# ESP32S2-new_sensor_device_template.net
KiCad netlist of a schematic drawn in EasyEDA
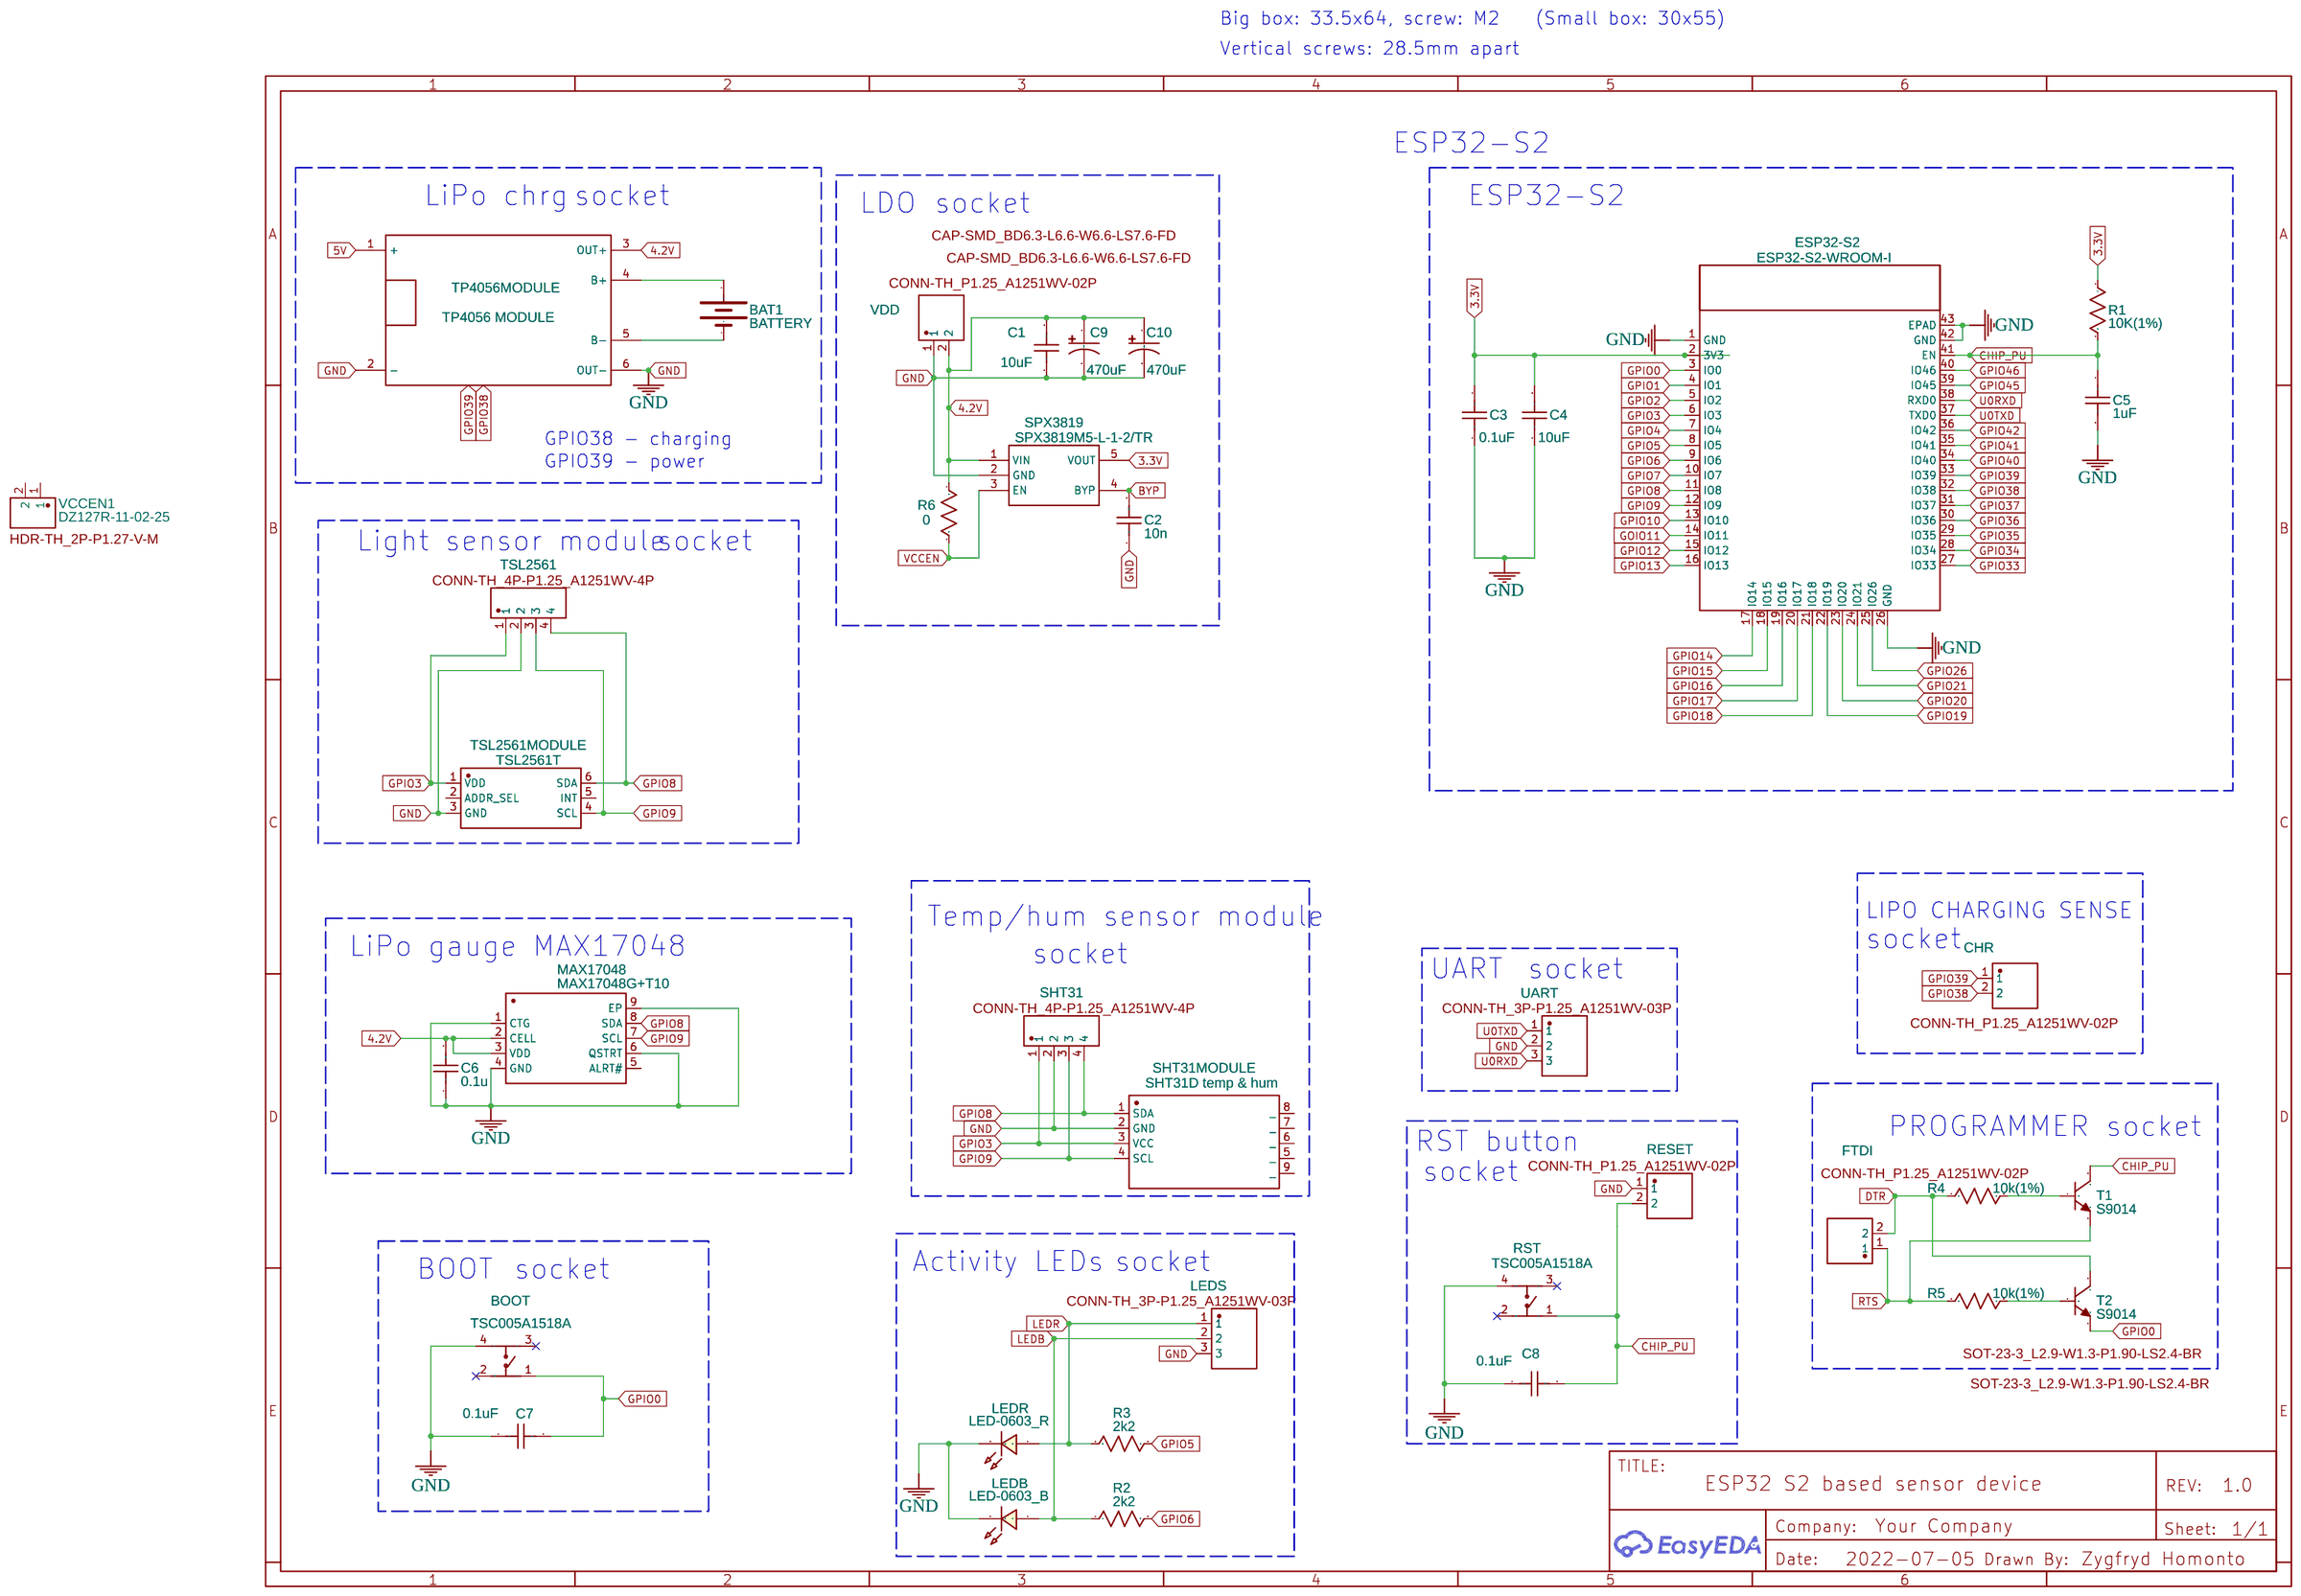
[diagram p0: schematic sheet]

(export (version "E")
  (design (tool "Eeschema 10.0.6"))
  (components
    (comp (ref "BAT1") (value "BATTERY") (libsource (lib "") (part "BATTERY")))
    (comp (ref "BOOT")
      (value "TSC005A1518A")
      (fields (field (name "BOM_Supplier Part") "C2888479"))
      (libsource (lib "") (part "TSC005A1518A"))
    )
    (comp (ref "C1") (value "10uF") (libsource (lib "") (part "C_0201_US_1")))
    (comp (ref "C2") (value "10n") (libsource (lib "") (part "C_0603_US")))
    (comp (ref "C3") (value "0.1uF") (libsource (lib "") (part "C_0201_US_1")))
    (comp (ref "C4") (value "10uF") (libsource (lib "") (part "C_0201_US_1")))
    (comp (ref "C5") (value "1uF") (libsource (lib "") (part "C_0201_US_2")))
    (comp (ref "C6") (value "0.1u") (libsource (lib "") (part "C_0603_US")))
    (comp (ref "C7") (value "0.1uF") (libsource (lib "") (part "C_0201_US")))
    (comp (ref "C8") (value "0.1uF") (libsource (lib "") (part "C_0201_US")))
    (comp (ref "C9")
      (value "470uF")
      (fields
        (field (name "BOM_Manufacturer Part") "BXJ-16V220-6.3*7.7")
        (field (name "BOM_Supplier Part") "C165635")
      )
      (libsource (lib "") (part "BXJ-16V220-6.3*7.7_1"))
    )
    (comp (ref "C10")
      (value "470uF")
      (fields
        (field (name "BOM_Manufacturer Part") "BXJ-16V220-6.3*7.7")
        (field (name "BOM_Supplier Part") "C165635")
      )
      (libsource (lib "") (part "BXJ-16V220-6.3*7.7"))
    )
    (comp (ref "CHR")
      (value "A1251WR-2P")
      (fields (field (name "BOM_Supplier Part") "C225097"))
      (libsource (lib "") (part "A1251WR-2P_3"))
    )
    (comp (ref "ESP32-S2")
      (value "ESP32-S2-WROOM-I")
      (fields (field (name "BOM_Manufacturer Part") "ESP32-S2-WROOM"))
      (libsource (lib "") (part "ESP32-S2-WROOM"))
    )
    (comp (ref "FTDI")
      (value "A1251WR-2P")
      (fields (field (name "BOM_Supplier Part") "C225097"))
      (libsource (lib "") (part "A1251WR-2P"))
    )
    (comp (ref "LEDB")
      (value "LED-0603_B")
      (fields
        (field (name "BOM_Manufacturer Part") "19-217/BHC-ZL1M2RY/3T")
        (field (name "BOM_Supplier Part") "C72041")
      )
      (libsource (lib "") (part "LED-0603_B"))
    )
    (comp (ref "LEDR")
      (value "LED-0603_R")
      (fields
        (field (name "BOM_Manufacturer Part") "19-217/R6C-AL1M2VY/3T")
        (field (name "BOM_Supplier Part") "C72044")
      )
      (libsource (lib "") (part "LED-0603_R"))
    )
    (comp (ref "LEDS")
      (value "A1251WR-3P")
      (fields (field (name "BOM_Supplier Part") "C225098"))
      (libsource (lib "") (part "A1251WR-3P_1"))
    )
    (comp (ref "MAX17048")
      (value "MAX17048G+T10")
      (fields (field (name "BOM_Supplier Part") "C2682616"))
      (libsource (lib "") (part "MAX17048G+T10"))
    )
    (comp (ref "R1") (value "10K(1%)") (libsource (lib "") (part "R_0201_US_1")))
    (comp (ref "R2") (value "2k2") (libsource (lib "") (part "R_0201_US")))
    (comp (ref "R3") (value "2k2") (libsource (lib "") (part "R_0201_US")))
    (comp (ref "R4") (value "10k(1%)") (libsource (lib "") (part "R_0201_US")))
    (comp (ref "R5") (value "10k(1%)") (libsource (lib "") (part "R_0201_US")))
    (comp (ref "R6") (value "0") (libsource (lib "") (part "R_0201_US_1")))
    (comp (ref "RESET")
      (value "A1251WR-2P")
      (fields (field (name "BOM_Supplier Part") "C225097"))
      (libsource (lib "") (part "A1251WR-2P_1"))
    )
    (comp (ref "RST")
      (value "TSC005A1518A")
      (fields (field (name "BOM_Supplier Part") "C2888479"))
      (libsource (lib "") (part "TSC005A1518A_1"))
    )
    (comp (ref "SHT31")
      (value "A1251WR-04P")
      (fields (field (name "BOM_Supplier Part") "C462094"))
      (libsource (lib "") (part "A1251WR-04P_1"))
    )
    (comp (ref "SHT31MODULE")
      (value "SHT31D temp & hum")
      (fields
        (field (name "BOM_Manufacturer Part") "SHT31-DIS-B")
        (field (name "BOM_Supplier Part") "C80862")
      )
      (libsource (lib "") (part "SHT31-DIS-B"))
    )
    (comp (ref "SPX3819")
      (value "SPX3819M5-L-1-2/TR")
      (fields (field (name "BOM_Supplier Part") "C54988"))
      (libsource (lib "") (part "SPX3819M5-L-1-2/TR"))
    )
    (comp (ref "T1")
      (value "S9014")
      (fields
        (field (name "BOM_Manufacturer Part") "S9014LT1 (S9014 J6)")
        (field (name "BOM_Supplier Part") "C2148")
      )
      (libsource (lib "") (part "S9014LT1 (S9014 J6)"))
    )
    (comp (ref "T2")
      (value "S9014")
      (fields
        (field (name "BOM_Manufacturer Part") "S9014LT1 (S9014 J6)")
        (field (name "BOM_Supplier Part") "C2148")
      )
      (libsource (lib "") (part "S9014LT1 (S9014 J6)_1"))
    )
    (comp (ref "TP4056MODULE") (value "TP4056 MODULE") (libsource (lib "") (part "TP4056 MODULE")))
    (comp (ref "TSL2561")
      (value "A1251WR-04P")
      (fields (field (name "BOM_Supplier Part") "C462094"))
      (libsource (lib "") (part "A1251WR-04P"))
    )
    (comp (ref "TSL2561MODULE")
      (value "TSL2561T")
      (fields (field (name "BOM_Supplier Part") "C481878"))
      (libsource (lib "") (part "TSL2561T"))
    )
    (comp (ref "UART")
      (value "A1251WR-3P")
      (fields (field (name "BOM_Supplier Part") "C225098"))
      (libsource (lib "") (part "A1251WR-3P"))
    )
    (comp (ref "VCCEN1")
      (value "DZ127R-11-02-25")
      (fields (field (name "BOM_Supplier Part") "C2935942"))
      (libsource (lib "") (part "DZ127R-11-02-25"))
    )
    (comp (ref "VDD")
      (value "A1251WR-2P")
      (fields (field (name "BOM_Supplier Part") "C225097"))
      (libsource (lib "") (part "A1251WR-2P_2"))
    )
  )
  (nets
    (net (code "1") (name "3.3V") (class "Default")
      (node (ref "C3") (pin "2") (pinfunction "2_2") (pintype "unspecified"))
      (node (ref "C4") (pin "2") (pinfunction "2_2") (pintype "unspecified"))
      (node (ref "ESP32-S2") (pin "2") (pinfunction "3V3_2") (pintype "unspecified"))
      (node (ref "R1") (pin "1") (pinfunction "1_1") (pintype "unspecified"))
      (node (ref "SPX3819") (pin "5") (pinfunction "VOUT_5") (pintype "unspecified"))
    )
    (net (code "2") (name "4.2V") (class "Default")
      (node (ref "C1") (pin "2") (pinfunction "2_2") (pintype "unspecified"))
      (node (ref "C10") (pin "1") (pinfunction "1_1") (pintype "unspecified"))
      (node (ref "C6") (pin "2") (pinfunction "2_2") (pintype "unspecified"))
      (node (ref "C9") (pin "1") (pinfunction "1_1") (pintype "unspecified"))
      (node (ref "MAX17048") (pin "2") (pinfunction "CELL_2") (pintype "unspecified"))
      (node (ref "MAX17048") (pin "3") (pinfunction "VDD_3") (pintype "unspecified"))
      (node (ref "R6") (pin "1") (pinfunction "1_1") (pintype "unspecified"))
      (node (ref "SPX3819") (pin "1") (pinfunction "VIN_1") (pintype "unspecified"))
      (node (ref "TP4056MODULE") (pin "3") (pinfunction "OUT+_3") (pintype "unspecified"))
      (node (ref "VDD") (pin "2") (pinfunction "2_2") (pintype "unspecified"))
    )
    (net (code "3") (name "5V") (class "Default")
      (node (ref "TP4056MODULE") (pin "1") (pinfunction "+_1") (pintype "unspecified"))
    )
    (net (code "4") (name "BYP") (class "Default")
      (node (ref "C2") (pin "2") (pinfunction "2_2") (pintype "unspecified"))
      (node (ref "SPX3819") (pin "4") (pinfunction "BYP_4") (pintype "unspecified"))
    )
    (net (code "5") (name "CHIP_PU") (class "Default")
      (node (ref "C5") (pin "1") (pinfunction "1_1") (pintype "unspecified"))
      (node (ref "C8") (pin "2") (pinfunction "2_2") (pintype "unspecified"))
      (node (ref "ESP32-S2") (pin "41") (pinfunction "EN_41") (pintype "unspecified"))
      (node (ref "R1") (pin "2") (pinfunction "2_2") (pintype "unspecified"))
      (node (ref "RESET") (pin "2") (pinfunction "2_2") (pintype "unspecified"))
      (node (ref "RST") (pin "1") (pinfunction "1_1") (pintype "unspecified"))
      (node (ref "T1") (pin "3") (pinfunction "C_3") (pintype "unspecified"))
    )
    (net (code "6") (name "DTR") (class "Default")
      (node (ref "FTDI") (pin "2") (pinfunction "2_2") (pintype "unspecified"))
      (node (ref "R4") (pin "1") (pinfunction "1_1") (pintype "unspecified"))
      (node (ref "T2") (pin "3") (pinfunction "C_3") (pintype "unspecified"))
    )
    (net (code "7") (name "GND") (class "Default")
      (node (ref "BOOT") (pin "4") (pinfunction "4_4") (pintype "unspecified"))
      (node (ref "C1") (pin "1") (pinfunction "1_1") (pintype "unspecified"))
      (node (ref "C10") (pin "2") (pinfunction "2_2") (pintype "unspecified"))
      (node (ref "C2") (pin "1") (pinfunction "1_1") (pintype "unspecified"))
      (node (ref "C3") (pin "1") (pinfunction "1_1") (pintype "unspecified"))
      (node (ref "C4") (pin "1") (pinfunction "1_1") (pintype "unspecified"))
      (node (ref "C5") (pin "2") (pinfunction "2_2") (pintype "unspecified"))
      (node (ref "C6") (pin "1") (pinfunction "1_1") (pintype "unspecified"))
      (node (ref "C7") (pin "1") (pinfunction "1_1") (pintype "unspecified"))
      (node (ref "C8") (pin "1") (pinfunction "1_1") (pintype "unspecified"))
      (node (ref "C9") (pin "2") (pinfunction "2_2") (pintype "unspecified"))
      (node (ref "ESP32-S2") (pin "1") (pinfunction "GND_1") (pintype "unspecified"))
      (node (ref "ESP32-S2") (pin "26") (pinfunction "GND_26") (pintype "unspecified"))
      (node (ref "ESP32-S2") (pin "42") (pinfunction "GND_42") (pintype "unspecified"))
      (node (ref "ESP32-S2") (pin "43") (pinfunction "EPAD_43") (pintype "unspecified"))
      (node (ref "LEDB") (pin "2") (pinfunction "2_2") (pintype "unspecified"))
      (node (ref "LEDR") (pin "2") (pinfunction "2_2") (pintype "unspecified"))
      (node (ref "LEDS") (pin "3") (pinfunction "3_3") (pintype "unspecified"))
      (node (ref "MAX17048") (pin "1") (pinfunction "CTG_1") (pintype "unspecified"))
      (node (ref "MAX17048") (pin "4") (pinfunction "GND_4") (pintype "unspecified"))
      (node (ref "MAX17048") (pin "6") (pinfunction "QSTRT_6") (pintype "unspecified"))
      (node (ref "MAX17048") (pin "9") (pinfunction "EP_9") (pintype "unspecified"))
      (node (ref "RESET") (pin "1") (pinfunction "1_1") (pintype "unspecified"))
      (node (ref "RST") (pin "4") (pinfunction "4_4") (pintype "unspecified"))
      (node (ref "SHT31") (pin "2") (pinfunction "2_2") (pintype "unspecified"))
      (node (ref "SHT31MODULE") (pin "2") (pinfunction "GND_2") (pintype "unspecified"))
      (node (ref "SPX3819") (pin "2") (pinfunction "GND_2") (pintype "unspecified"))
      (node (ref "TP4056MODULE") (pin "2") (pinfunction "-_2") (pintype "unspecified"))
      (node (ref "TP4056MODULE") (pin "6") (pinfunction "OUT-_6") (pintype "unspecified"))
      (node (ref "TSL2561") (pin "2") (pinfunction "2_2") (pintype "unspecified"))
      (node (ref "TSL2561MODULE") (pin "3") (pinfunction "GND_3") (pintype "unspecified"))
      (node (ref "UART") (pin "2") (pinfunction "2_2") (pintype "unspecified"))
      (node (ref "VDD") (pin "1") (pinfunction "1_1") (pintype "unspecified"))
    )
    (net (code "8") (name "GOIO11") (class "Default")
      (node (ref "ESP32-S2") (pin "14") (pinfunction "IO11_14") (pintype "unspecified"))
    )
    (net (code "9") (name "GPIO0") (class "Default")
      (node (ref "BOOT") (pin "1") (pinfunction "1_1") (pintype "unspecified"))
      (node (ref "C7") (pin "2") (pinfunction "2_2") (pintype "unspecified"))
      (node (ref "ESP32-S2") (pin "3") (pinfunction "IO0_3") (pintype "unspecified"))
      (node (ref "T2") (pin "2") (pinfunction "E_2") (pintype "unspecified"))
    )
    (net (code "10") (name "GPIO1") (class "Default")
      (node (ref "ESP32-S2") (pin "4") (pinfunction "IO1_4") (pintype "unspecified"))
    )
    (net (code "11") (name "GPIO2") (class "Default")
      (node (ref "ESP32-S2") (pin "5") (pinfunction "IO2_5") (pintype "unspecified"))
    )
    (net (code "12") (name "GPIO3") (class "Default")
      (node (ref "ESP32-S2") (pin "6") (pinfunction "IO3_6") (pintype "unspecified"))
      (node (ref "SHT31") (pin "1") (pinfunction "1_1") (pintype "unspecified"))
      (node (ref "SHT31MODULE") (pin "3") (pinfunction "VCC_3") (pintype "unspecified"))
      (node (ref "TSL2561") (pin "1") (pinfunction "1_1") (pintype "unspecified"))
      (node (ref "TSL2561MODULE") (pin "1") (pinfunction "VDD_1") (pintype "unspecified"))
    )
    (net (code "13") (name "GPIO4") (class "Default")
      (node (ref "ESP32-S2") (pin "7") (pinfunction "IO4_7") (pintype "unspecified"))
    )
    (net (code "14") (name "GPIO5") (class "Default")
      (node (ref "ESP32-S2") (pin "8") (pinfunction "IO5_8") (pintype "unspecified"))
      (node (ref "R3") (pin "2") (pinfunction "2_2") (pintype "unspecified"))
    )
    (net (code "15") (name "GPIO6") (class "Default")
      (node (ref "ESP32-S2") (pin "9") (pinfunction "IO6_9") (pintype "unspecified"))
      (node (ref "R2") (pin "2") (pinfunction "2_2") (pintype "unspecified"))
    )
    (net (code "16") (name "GPIO7") (class "Default")
      (node (ref "ESP32-S2") (pin "10") (pinfunction "IO7_10") (pintype "unspecified"))
    )
    (net (code "17") (name "GPIO8") (class "Default")
      (node (ref "ESP32-S2") (pin "11") (pinfunction "IO8_11") (pintype "unspecified"))
      (node (ref "MAX17048") (pin "8") (pinfunction "SDA_8") (pintype "unspecified"))
      (node (ref "SHT31") (pin "4") (pinfunction "4_4") (pintype "unspecified"))
      (node (ref "SHT31MODULE") (pin "1") (pinfunction "SDA_1") (pintype "unspecified"))
      (node (ref "TSL2561") (pin "4") (pinfunction "4_4") (pintype "unspecified"))
      (node (ref "TSL2561MODULE") (pin "6") (pinfunction "SDA_6") (pintype "unspecified"))
    )
    (net (code "18") (name "GPIO9") (class "Default")
      (node (ref "ESP32-S2") (pin "12") (pinfunction "IO9_12") (pintype "unspecified"))
      (node (ref "MAX17048") (pin "7") (pinfunction "SCL_7") (pintype "unspecified"))
      (node (ref "SHT31") (pin "3") (pinfunction "3_3") (pintype "unspecified"))
      (node (ref "SHT31MODULE") (pin "4") (pinfunction "SCL_4") (pintype "unspecified"))
      (node (ref "TSL2561") (pin "3") (pinfunction "3_3") (pintype "unspecified"))
      (node (ref "TSL2561MODULE") (pin "4") (pinfunction "SCL_4") (pintype "unspecified"))
    )
    (net (code "19") (name "GPIO10") (class "Default")
      (node (ref "ESP32-S2") (pin "13") (pinfunction "IO10_13") (pintype "unspecified"))
    )
    (net (code "20") (name "GPIO12") (class "Default")
      (node (ref "ESP32-S2") (pin "15") (pinfunction "IO12_15") (pintype "unspecified"))
    )
    (net (code "21") (name "GPIO13") (class "Default")
      (node (ref "ESP32-S2") (pin "16") (pinfunction "IO13_16") (pintype "unspecified"))
    )
    (net (code "22") (name "GPIO14") (class "Default")
      (node (ref "ESP32-S2") (pin "17") (pinfunction "IO14_17") (pintype "unspecified"))
    )
    (net (code "23") (name "GPIO15") (class "Default")
      (node (ref "ESP32-S2") (pin "18") (pinfunction "IO15_18") (pintype "unspecified"))
    )
    (net (code "24") (name "GPIO16") (class "Default")
      (node (ref "ESP32-S2") (pin "19") (pinfunction "IO16_19") (pintype "unspecified"))
    )
    (net (code "25") (name "GPIO17") (class "Default")
      (node (ref "ESP32-S2") (pin "20") (pinfunction "IO17_20") (pintype "unspecified"))
    )
    (net (code "26") (name "GPIO18") (class "Default")
      (node (ref "ESP32-S2") (pin "21") (pinfunction "IO18_21") (pintype "unspecified"))
    )
    (net (code "27") (name "GPIO19") (class "Default")
      (node (ref "ESP32-S2") (pin "22") (pinfunction "IO19_22") (pintype "unspecified"))
    )
    (net (code "28") (name "GPIO20") (class "Default")
      (node (ref "ESP32-S2") (pin "23") (pinfunction "IO20_23") (pintype "unspecified"))
    )
    (net (code "29") (name "GPIO21") (class "Default")
      (node (ref "ESP32-S2") (pin "24") (pinfunction "IO21_24") (pintype "unspecified"))
    )
    (net (code "30") (name "GPIO26") (class "Default")
      (node (ref "ESP32-S2") (pin "25") (pinfunction "IO26_25") (pintype "unspecified"))
    )
    (net (code "31") (name "GPIO33") (class "Default")
      (node (ref "ESP32-S2") (pin "27") (pinfunction "IO33_27") (pintype "unspecified"))
    )
    (net (code "32") (name "GPIO34") (class "Default")
      (node (ref "ESP32-S2") (pin "28") (pinfunction "IO34_28") (pintype "unspecified"))
    )
    (net (code "33") (name "GPIO35") (class "Default")
      (node (ref "ESP32-S2") (pin "29") (pinfunction "IO35_29") (pintype "unspecified"))
    )
    (net (code "34") (name "GPIO36") (class "Default")
      (node (ref "ESP32-S2") (pin "30") (pinfunction "IO36_30") (pintype "unspecified"))
    )
    (net (code "35") (name "GPIO37") (class "Default")
      (node (ref "ESP32-S2") (pin "31") (pinfunction "IO37_31") (pintype "unspecified"))
    )
    (net (code "36") (name "GPIO38") (class "Default")
      (node (ref "CHR") (pin "2") (pinfunction "2_2") (pintype "unspecified"))
      (node (ref "ESP32-S2") (pin "32") (pinfunction "IO38_32") (pintype "unspecified"))
    )
    (net (code "37") (name "GPIO39") (class "Default")
      (node (ref "CHR") (pin "1") (pinfunction "1_1") (pintype "unspecified"))
      (node (ref "ESP32-S2") (pin "33") (pinfunction "IO39_33") (pintype "unspecified"))
    )
    (net (code "38") (name "GPIO40") (class "Default")
      (node (ref "ESP32-S2") (pin "34") (pinfunction "IO40_34") (pintype "unspecified"))
    )
    (net (code "39") (name "GPIO41") (class "Default")
      (node (ref "ESP32-S2") (pin "35") (pinfunction "IO41_35") (pintype "unspecified"))
    )
    (net (code "40") (name "GPIO42") (class "Default")
      (node (ref "ESP32-S2") (pin "36") (pinfunction "IO42_36") (pintype "unspecified"))
    )
    (net (code "41") (name "GPIO45") (class "Default")
      (node (ref "ESP32-S2") (pin "39") (pinfunction "IO45_39") (pintype "unspecified"))
    )
    (net (code "42") (name "GPIO46") (class "Default")
      (node (ref "ESP32-S2") (pin "40") (pinfunction "IO46_40") (pintype "unspecified"))
    )
    (net (code "43") (name "LEDB") (class "Default")
      (node (ref "LEDB") (pin "1") (pinfunction "1_1") (pintype "unspecified"))
      (node (ref "LEDS") (pin "2") (pinfunction "2_2") (pintype "unspecified"))
      (node (ref "R2") (pin "1") (pinfunction "1_1") (pintype "unspecified"))
    )
    (net (code "44") (name "LEDR") (class "Default")
      (node (ref "LEDR") (pin "1") (pinfunction "1_1") (pintype "unspecified"))
      (node (ref "LEDS") (pin "1") (pinfunction "1_1") (pintype "unspecified"))
      (node (ref "R3") (pin "1") (pinfunction "1_1") (pintype "unspecified"))
    )
    (net (code "45") (name "Net-(T1-B)") (class "Default")
      (node (ref "R4") (pin "2") (pinfunction "2_2") (pintype "unspecified"))
      (node (ref "T1") (pin "1") (pinfunction "B_1") (pintype "unspecified"))
    )
    (net (code "46") (name "Net-(T2-B)") (class "Default")
      (node (ref "R5") (pin "2") (pinfunction "2_2") (pintype "unspecified"))
      (node (ref "T2") (pin "1") (pinfunction "B_1") (pintype "unspecified"))
    )
    (net (code "47") (name "Net-(TP4056MODULE-B+)") (class "Default")
      (node (ref "BAT1") (pin "+") (pinfunction "+_+") (pintype "passive"))
      (node (ref "TP4056MODULE") (pin "4") (pinfunction "B+_4") (pintype "unspecified"))
    )
    (net (code "48") (name "Net-(TP4056MODULE-B-)") (class "Default")
      (node (ref "BAT1") (pin "-") (pinfunction "-_-") (pintype "passive"))
      (node (ref "TP4056MODULE") (pin "5") (pinfunction "B-_5") (pintype "unspecified"))
    )
    (net (code "49") (name "RTS") (class "Default")
      (node (ref "FTDI") (pin "1") (pinfunction "1_1") (pintype "unspecified"))
      (node (ref "R5") (pin "1") (pinfunction "1_1") (pintype "unspecified"))
      (node (ref "T1") (pin "2") (pinfunction "E_2") (pintype "unspecified"))
    )
    (net (code "50") (name "U0RXD") (class "Default")
      (node (ref "ESP32-S2") (pin "38") (pinfunction "RXD0_38") (pintype "unspecified"))
      (node (ref "UART") (pin "3") (pinfunction "3_3") (pintype "unspecified"))
    )
    (net (code "51") (name "U0TXD") (class "Default")
      (node (ref "ESP32-S2") (pin "37") (pinfunction "TXD0_37") (pintype "unspecified"))
      (node (ref "UART") (pin "1") (pinfunction "1_1") (pintype "unspecified"))
    )
    (net (code "52") (name "VCCEN") (class "Default")
      (node (ref "R6") (pin "2") (pinfunction "2_2") (pintype "unspecified"))
      (node (ref "SPX3819") (pin "3") (pinfunction "EN_3") (pintype "unspecified"))
    )
    (net (code "53") (name "unconnected-(BOOT-Pad2)") (class "Default")
      (node (ref "BOOT") (pin "2") (pinfunction "2_2") (pintype "unspecified+no_connect"))
    )
    (net (code "54") (name "unconnected-(BOOT-Pad3)") (class "Default")
      (node (ref "BOOT") (pin "3") (pinfunction "3_3") (pintype "unspecified+no_connect"))
    )
    (net (code "55") (name "unconnected-(MAX17048-ALRT#-Pad5)") (class "Default")
      (node (ref "MAX17048") (pin "5") (pinfunction "ALRT#_5") (pintype "unspecified"))
    )
    (net (code "56") (name "unconnected-(RST-Pad2)") (class "Default")
      (node (ref "RST") (pin "2") (pinfunction "2_2") (pintype "unspecified+no_connect"))
    )
    (net (code "57") (name "unconnected-(RST-Pad3)") (class "Default")
      (node (ref "RST") (pin "3") (pinfunction "3_3") (pintype "unspecified+no_connect"))
    )
    (net (code "58") (name "unconnected-(SHT31MODULE-_-Pad5)") (class "Default")
      (node (ref "SHT31MODULE") (pin "5") (pinfunction "__5") (pintype "unspecified"))
    )
    (net (code "59") (name "unconnected-(SHT31MODULE-_-Pad6)") (class "Default")
      (node (ref "SHT31MODULE") (pin "6") (pinfunction "__6") (pintype "unspecified"))
    )
    (net (code "60") (name "unconnected-(SHT31MODULE-_-Pad7)") (class "Default")
      (node (ref "SHT31MODULE") (pin "7") (pinfunction "__7") (pintype "unspecified"))
    )
    (net (code "61") (name "unconnected-(SHT31MODULE-_-Pad8)") (class "Default")
      (node (ref "SHT31MODULE") (pin "8") (pinfunction "__8") (pintype "unspecified"))
    )
    (net (code "62") (name "unconnected-(SHT31MODULE-_-Pad9)") (class "Default")
      (node (ref "SHT31MODULE") (pin "9") (pinfunction "__9") (pintype "unspecified"))
    )
    (net (code "63") (name "unconnected-(TSL2561MODULE-ADDR_SEL-Pad2)") (class "Default")
      (node (ref "TSL2561MODULE") (pin "2") (pinfunction "ADDR_SEL_2") (pintype "unspecified"))
    )
    (net (code "64") (name "unconnected-(TSL2561MODULE-INT-Pad5)") (class "Default")
      (node (ref "TSL2561MODULE") (pin "5") (pinfunction "INT_5") (pintype "unspecified"))
    )
    (net (code "65") (name "unconnected-(VCCEN1-Pad1)") (class "Default")
      (node (ref "VCCEN1") (pin "1") (pinfunction "1_1") (pintype "unspecified"))
    )
    (net (code "66") (name "unconnected-(VCCEN1-Pad2)") (class "Default")
      (node (ref "VCCEN1") (pin "2") (pinfunction "2_2") (pintype "unspecified"))
    )
  )
)
